# OTHERS.net
KiCad netlist of a schematic drawn in Altium Designer
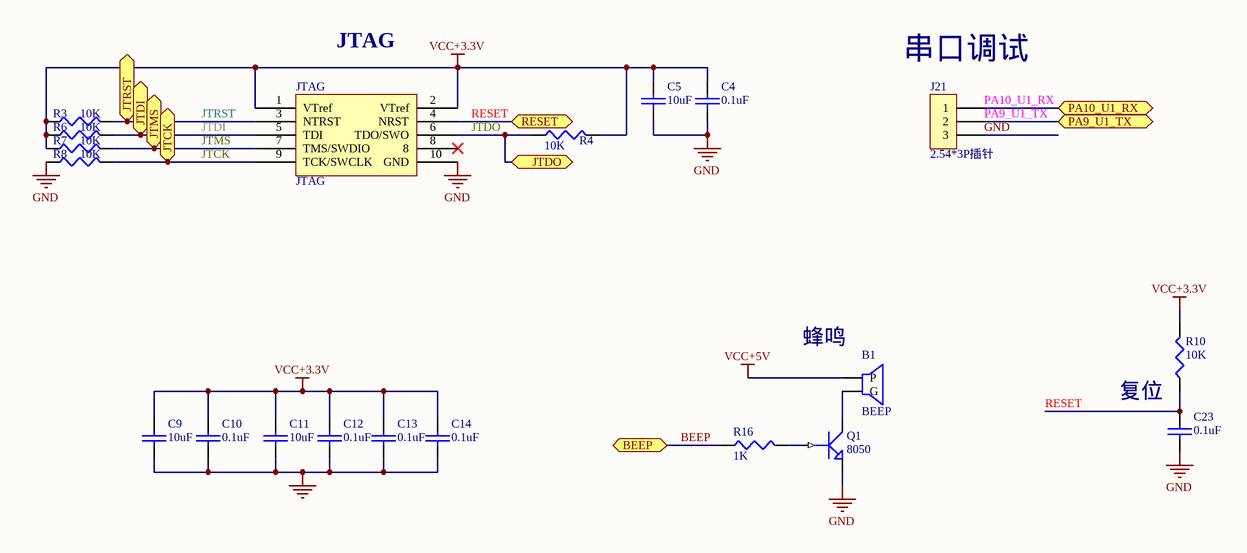
[diagram p0: OTHERS.SchDoc]

(export (version "E")
  (design (tool "Eeschema 10.0.6"))
  (components
    (comp (ref "B1")
      (value "BEEP")
      (footprint "BEEP-W")
      (description "TMB12A05  5V有源电磁蜂鸣器")
      (libsource (lib "INSPUR_PCB") (part "BEEP"))
    )
    (comp (ref "C4")
      (value "0.1uF")
      (footprint "0603")
      (description "0603陶瓷贴片电容")
      (libsource (lib "INSPUR_PCB") (part "CAP-0603"))
    )
    (comp (ref "C5")
      (value "10uF")
      (footprint "0805")
      (description "0805陶瓷贴片电容")
      (libsource (lib "INSPUR_PCB") (part "CAP-0805"))
    )
    (comp (ref "C9")
      (value "10uF")
      (footprint "0805")
      (description "0805陶瓷贴片电容")
      (libsource (lib "INSPUR_PCB") (part "CAP-0805"))
    )
    (comp (ref "C10")
      (value "0.1uF")
      (footprint "0603")
      (description "0603陶瓷贴片电容")
      (libsource (lib "INSPUR_PCB") (part "CAP-0603"))
    )
    (comp (ref "C11")
      (value "10uF")
      (footprint "0805")
      (description "0805陶瓷贴片电容")
      (libsource (lib "INSPUR_PCB") (part "CAP-0805"))
    )
    (comp (ref "C12")
      (value "0.1uF")
      (footprint "0603")
      (description "0603陶瓷贴片电容")
      (libsource (lib "INSPUR_PCB") (part "CAP-0603"))
    )
    (comp (ref "C13")
      (value "0.1uF")
      (footprint "0603")
      (description "0603陶瓷贴片电容")
      (libsource (lib "INSPUR_PCB") (part "CAP-0603"))
    )
    (comp (ref "C14")
      (value "0.1uF")
      (footprint "0603")
      (description "0603陶瓷贴片电容")
      (libsource (lib "INSPUR_PCB") (part "CAP-0603"))
    )
    (comp (ref "C23")
      (value "0.1uF")
      (footprint "0603")
      (description "0603陶瓷贴片电容")
      (libsource (lib "INSPUR_PCB") (part "CAP-0603"))
    )
    (comp (ref "J21")
      (value "2.54*3P插针")
      (footprint "2.54-TX")
      (description "2.54mm*3P单排插针")
      (libsource (lib "INSPUR_PCB") (part "2.54*3P插针"))
    )
    (comp (ref "JTAG")
      (value "JTAG")
      (footprint "JTAG_10")
      (description "2.54*5*2   2.54mm 5P双排排阵")
      (libsource (lib "INSPUR_PCB") (part "JTAG"))
    )
    (comp (ref "Q1")
      (value "8050")
      (footprint "SOT-23")
      (description "8050 NPN型三极管")
      (libsource (lib "INSPUR_PCB") (part "8050"))
    )
    (comp (ref "R3")
      (value "10K")
      (footprint "0603")
      (description "陶瓷贴片电阻0603封装")
      (libsource (lib "INSPUR_PCB") (part "RES-0603"))
    )
    (comp (ref "R4")
      (value "10K")
      (footprint "0603")
      (description "陶瓷贴片电阻0603封装")
      (libsource (lib "INSPUR_PCB") (part "RES-0603"))
    )
    (comp (ref "R6")
      (value "10K")
      (footprint "0603")
      (description "陶瓷贴片电阻0603封装")
      (libsource (lib "INSPUR_PCB") (part "RES-0603"))
    )
    (comp (ref "R7")
      (value "10K")
      (footprint "0603")
      (description "陶瓷贴片电阻0603封装")
      (libsource (lib "INSPUR_PCB") (part "RES-0603"))
    )
    (comp (ref "R8")
      (value "10K")
      (footprint "0603")
      (description "陶瓷贴片电阻0603封装")
      (libsource (lib "INSPUR_PCB") (part "RES-0603"))
    )
    (comp (ref "R10")
      (value "10K")
      (footprint "0603")
      (description "陶瓷贴片电阻0603封装")
      (libsource (lib "INSPUR_PCB") (part "RES-0603"))
    )
    (comp (ref "R16")
      (value "1K")
      (footprint "0603")
      (description "陶瓷贴片电阻0603封装")
      (libsource (lib "INSPUR_PCB") (part "RES-0603"))
    )
  )
  (nets
    (net (code "1") (name "/BEEP") (class "Default")
      (node (ref "R16") (pin "1") (pinfunction "1_1") (pintype "passive"))
    )
    (net (code "2") (name "/JTCK") (class "Default")
      (node (ref "JTAG") (pin "9") (pinfunction "TCK/SWCLK_9") (pintype "passive"))
      (node (ref "R8") (pin "2") (pinfunction "2_2") (pintype "passive"))
    )
    (net (code "3") (name "/JTDI") (class "Default")
      (node (ref "JTAG") (pin "5") (pinfunction "TDI_5") (pintype "passive"))
      (node (ref "R6") (pin "2") (pinfunction "2_2") (pintype "passive"))
    )
    (net (code "4") (name "/JTDO") (class "Default")
      (node (ref "JTAG") (pin "6") (pinfunction "TDO/SWO_6") (pintype "passive"))
      (node (ref "R4") (pin "1") (pinfunction "1_1") (pintype "passive"))
    )
    (net (code "5") (name "/JTMS") (class "Default")
      (node (ref "JTAG") (pin "7") (pinfunction "TMS/SWDIO_7") (pintype "passive"))
      (node (ref "R7") (pin "2") (pinfunction "2_2") (pintype "passive"))
    )
    (net (code "6") (name "/JTRST") (class "Default")
      (node (ref "JTAG") (pin "3") (pinfunction "NTRST_3") (pintype "passive"))
      (node (ref "R3") (pin "2") (pinfunction "2_2") (pintype "passive"))
    )
    (net (code "7") (name "/PA9_U1_TX") (class "Default")
      (node (ref "J21") (pin "2") (pinfunction "2_2") (pintype "passive"))
    )
    (net (code "8") (name "/PA10_U1_RX") (class "Default")
      (node (ref "J21") (pin "1") (pinfunction "1_1") (pintype "passive"))
    )
    (net (code "9") (name "/RESET") (class "Default")
      (node (ref "C23") (pin "2") (pinfunction "2_2") (pintype "passive"))
      (node (ref "JTAG") (pin "4") (pinfunction "NRST_4") (pintype "passive"))
      (node (ref "R10") (pin "1") (pinfunction "1_1") (pintype "passive"))
    )
    (net (code "10") (name "GND") (class "Default")
      (node (ref "C10") (pin "1") (pinfunction "1_1") (pintype "passive"))
      (node (ref "C11") (pin "2") (pinfunction "2_2") (pintype "passive"))
      (node (ref "C12") (pin "1") (pinfunction "1_1") (pintype "passive"))
      (node (ref "C13") (pin "1") (pinfunction "1_1") (pintype "passive"))
      (node (ref "C14") (pin "1") (pinfunction "1_1") (pintype "passive"))
      (node (ref "C23") (pin "1") (pinfunction "1_1") (pintype "passive"))
      (node (ref "C4") (pin "1") (pinfunction "1_1") (pintype "passive"))
      (node (ref "C5") (pin "2") (pinfunction "2_2") (pintype "passive"))
      (node (ref "C9") (pin "2") (pinfunction "2_2") (pintype "passive"))
      (node (ref "J21") (pin "3") (pinfunction "3_3") (pintype "passive"))
      (node (ref "JTAG") (pin "10") (pinfunction "GND_10") (pintype "passive"))
      (node (ref "Q1") (pin "2") (pinfunction "E_2") (pintype "passive"))
      (node (ref "R8") (pin "1") (pinfunction "1_1") (pintype "passive"))
    )
    (net (code "11") (name "Net-(B1-G)") (class "Default")
      (node (ref "B1") (pin "2") (pinfunction "G_2") (pintype "passive"))
      (node (ref "Q1") (pin "3") (pinfunction "C_3") (pintype "passive"))
    )
    (net (code "12") (name "Net-(Q1-B)") (class "Default")
      (node (ref "Q1") (pin "1") (pinfunction "B_1") (pintype "input"))
      (node (ref "R16") (pin "2") (pinfunction "2_2") (pintype "passive"))
    )
    (net (code "13") (name "VCC+3.3V") (class "Default")
      (node (ref "C10") (pin "2") (pinfunction "2_2") (pintype "passive"))
      (node (ref "C11") (pin "1") (pinfunction "1_1") (pintype "passive"))
      (node (ref "C12") (pin "2") (pinfunction "2_2") (pintype "passive"))
      (node (ref "C13") (pin "2") (pinfunction "2_2") (pintype "passive"))
      (node (ref "C14") (pin "2") (pinfunction "2_2") (pintype "passive"))
      (node (ref "C4") (pin "2") (pinfunction "2_2") (pintype "passive"))
      (node (ref "C5") (pin "1") (pinfunction "1_1") (pintype "passive"))
      (node (ref "C9") (pin "1") (pinfunction "1_1") (pintype "passive"))
      (node (ref "JTAG") (pin "1") (pinfunction "VTref_1") (pintype "passive"))
      (node (ref "JTAG") (pin "2") (pinfunction "VTref_2") (pintype "passive"))
      (node (ref "R10") (pin "2") (pinfunction "2_2") (pintype "passive"))
      (node (ref "R3") (pin "1") (pinfunction "1_1") (pintype "passive"))
      (node (ref "R4") (pin "2") (pinfunction "2_2") (pintype "passive"))
      (node (ref "R6") (pin "1") (pinfunction "1_1") (pintype "passive"))
      (node (ref "R7") (pin "1") (pinfunction "1_1") (pintype "passive"))
    )
    (net (code "14") (name "VCC+5V") (class "Default")
      (node (ref "B1") (pin "1") (pinfunction "P_1") (pintype "passive"))
    )
    (net (code "15") (name "unconnected-(JTAG-Pad8)") (class "Default")
      (node (ref "JTAG") (pin "8") (pinfunction "8_8") (pintype "passive+no_connect"))
    )
  )
)
